# 1_1_MOC_Channel.net
KiCad netlist of a schematic drawn in Altium Designer
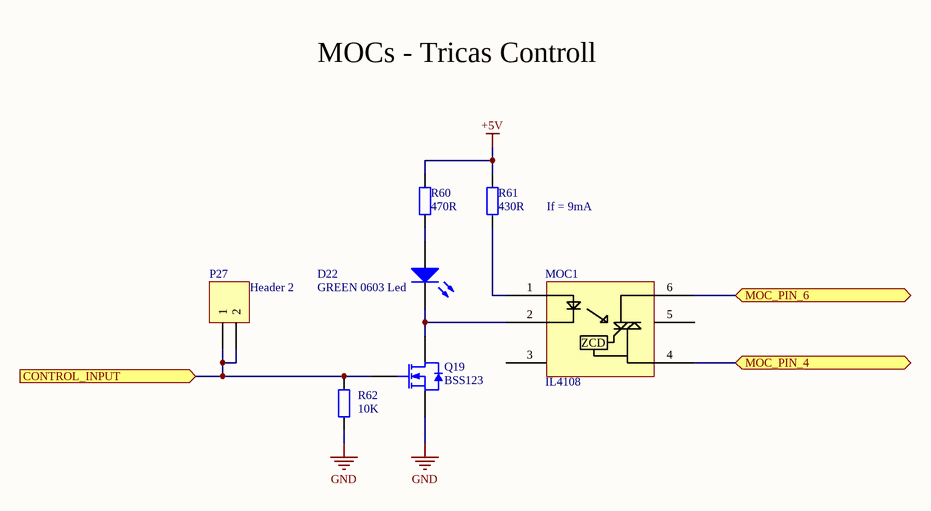
[diagram p0: [1.1]MOC_Channel.SchDoc]

(export (version "E")
  (design (tool "Eeschema 10.0.6"))
  (components
    (comp (ref "D22")
      (value "GREEN 0603 Led")
      (footprint "LED0603")
      (description "Typical INFRARED GaAs LED")
      (fields
        (field (name "MANUFACTURER PART NO.") "KPT-1608CGCK")
        (field (name "PUBLISHER") "Altium Limited")
      )
      (libsource (lib "Miscellaneous Devices") (part "LED0"))
    )
    (comp (ref "MOC1")
      (value "IL4108")
      (footprint "DIP-6")
      (description "Optoisolators Trica Driver Output, With Zero Cross Detect")
      (libsource (lib "ROV_Voltage_Switch") (part "MOC306x"))
    )
    (comp (ref "P27")
      (value "Header 2")
      (footprint "HDR1X2")
      (description "Header, 2-Pin")
      (fields (field (name "PUBLISHER") "Altium Limited"))
      (libsource (lib "Miscellaneous Connectors") (part "Header 2"))
    )
    (comp (ref "Q19")
      (value "BSS123")
      (footprint "SOT23_N")
      (description "N-channel Enhancement Mode Vertical D-MOSFET")
      (fields (field (name "PUBLISHER") "Altium Limited"))
      (libsource (lib "Philips Discrete MOSFET - Low Power") (part "BSS123"))
    )
    (comp (ref "R60")
      (value "470R")
      (footprint "J1-0603")
      (description "Resistor")
      (fields (field (name "Comment") "0603") (field (name "PUBLISHER") "Altium Limited"))
      (libsource (lib "Miscellaneous Devices") (part "Res2"))
    )
    (comp (ref "R61")
      (value "430R")
      (footprint "J1-0603")
      (description "Resistor")
      (fields (field (name "Comment") "0603") (field (name "PUBLISHER") "Altium Limited"))
      (libsource (lib "Miscellaneous Devices") (part "Res2"))
    )
    (comp (ref "R62")
      (value "10K")
      (footprint "J1-0603")
      (description "Resistor")
      (fields (field (name "Comment") "0603") (field (name "PUBLISHER") "Altium Limited"))
      (libsource (lib "Miscellaneous Devices") (part "Res2"))
    )
  )
  (nets
    (net (code "1") (name "+5V") (class "Default")
      (node (ref "R60") (pin "2") (pinfunction "2_2") (pintype "passive"))
      (node (ref "R61") (pin "2") (pinfunction "2_2") (pintype "passive"))
    )
    (net (code "2") (name "/CONTROL_INPUT") (class "Default")
      (node (ref "P27") (pin "1") (pinfunction "1_1") (pintype "passive"))
      (node (ref "P27") (pin "2") (pinfunction "2_2") (pintype "passive"))
      (node (ref "Q19") (pin "1") (pinfunction "G_1") (pintype "passive"))
      (node (ref "R62") (pin "2") (pinfunction "2_2") (pintype "passive"))
    )
    (net (code "3") (name "/MOC_PIN_4") (class "Default")
      (node (ref "MOC1") (pin "4") (pinfunction "E_4") (pintype "passive"))
    )
    (net (code "4") (name "/MOC_PIN_6") (class "Default")
      (node (ref "MOC1") (pin "6") (pinfunction "B_6") (pintype "passive"))
    )
    (net (code "5") (name "GND") (class "Default")
      (node (ref "Q19") (pin "2") (pinfunction "S_2") (pintype "passive"))
      (node (ref "R62") (pin "1") (pinfunction "1_1") (pintype "passive"))
    )
    (net (code "6") (name "Net-(D22-A)") (class "Default")
      (node (ref "D22") (pin "1") (pinfunction "A_1") (pintype "passive"))
      (node (ref "R60") (pin "1") (pinfunction "1_1") (pintype "passive"))
    )
    (net (code "7") (name "Net-(D22-K)") (class "Default")
      (node (ref "D22") (pin "2") (pinfunction "K_2") (pintype "passive"))
      (node (ref "MOC1") (pin "2") (pinfunction "C_2") (pintype "passive"))
      (node (ref "Q19") (pin "3") (pinfunction "D_3") (pintype "passive"))
    )
    (net (code "8") (name "Net-(MOC1-A)") (class "Default")
      (node (ref "MOC1") (pin "1") (pinfunction "A_1") (pintype "passive"))
      (node (ref "R61") (pin "1") (pinfunction "1_1") (pintype "passive"))
    )
    (net (code "9") (name "unconnected-(MOC1-C-Pad5)") (class "Default")
      (node (ref "MOC1") (pin "5") (pinfunction "C_5") (pintype "passive"))
    )
    (net (code "10") (name "unconnected-(MOC1-NC-Pad3)") (class "Default")
      (node (ref "MOC1") (pin "3") (pinfunction "NC_3") (pintype "passive"))
    )
  )
)
